# production.net
KiCad netlist of a schematic drawn in EAGLE
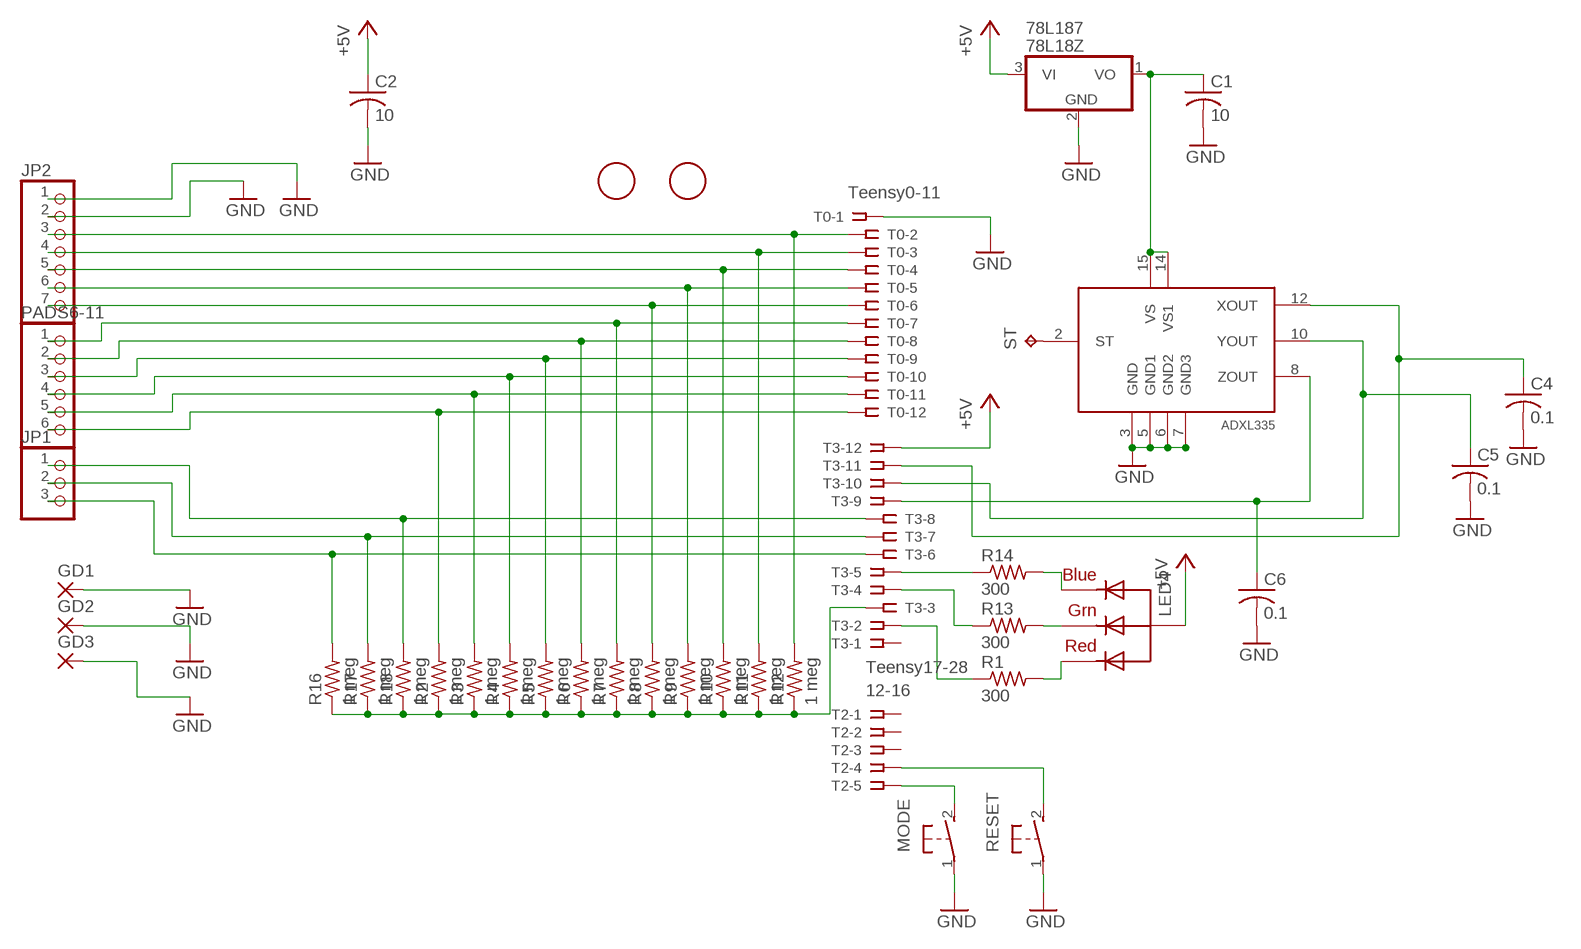
[diagram p0: schematic, sheet 1]

(export (version "E")
  (design (tool "Eeschema 10.0.6"))
  (components
    (comp (ref "78L187")
      (value "78L18Z")
      (footprint "eagle-import:TO92")
      (libsource (lib "eagle-import") (part "78ZL18"))
    )
    (comp (ref "ADXL335")
      (value "ADXL33X")
      (footprint "eagle-import:16LCSP")
      (libsource (lib "eagle-import") (part "ADXL33X"))
    )
    (comp (ref "C1")
      (value "10")
      (footprint "eagle-import:C050-024X044")
      (libsource (lib "eagle-import") (part "C-US050-024X044"))
    )
    (comp (ref "C2")
      (value "10")
      (footprint "eagle-import:C050-024X044")
      (libsource (lib "eagle-import") (part "C-US050-024X044"))
    )
    (comp (ref "C4")
      (value "0.1")
      (footprint "eagle-import:C050-024X044")
      (libsource (lib "eagle-import") (part "C-US050-024X044"))
    )
    (comp (ref "C5")
      (value "0.1")
      (footprint "eagle-import:C050-024X044")
      (libsource (lib "eagle-import") (part "C-US050-024X044"))
    )
    (comp (ref "C6")
      (value "0.1")
      (footprint "eagle-import:C050-024X044")
      (libsource (lib "eagle-import") (part "C-US050-024X044"))
    )
    (comp (ref "FID1")
      (value "FIDUCIAL")
      (footprint "eagle-import:FIDUCIAL_1MM")
      (libsource (lib "eagle-import") (part "FIDUCIAL"))
    )
    (comp (ref "FID2")
      (value "FIDUCIAL")
      (footprint "eagle-import:FIDUCIAL_1MM")
      (libsource (lib "eagle-import") (part "FIDUCIAL"))
    )
    (comp (ref "GD1")
      (value "3,17/1,1")
      (footprint "eagle-import:3,17_1,1")
      (libsource (lib "eagle-import") (part "3,17/1,1"))
    )
    (comp (ref "GD2")
      (value "3,17/1,1")
      (footprint "eagle-import:3,17_1,1")
      (libsource (lib "eagle-import") (part "3,17/1,1"))
    )
    (comp (ref "GD3")
      (value "3,17/1,1")
      (footprint "eagle-import:3,17_1,1")
      (libsource (lib "eagle-import") (part "3,17/1,1"))
    )
    (comp (ref "JP1")
      (value "PINHD-1X3")
      (footprint "eagle-import:1X03")
      (libsource (lib "eagle-import") (part "PINHD-1X3"))
    )
    (comp (ref "JP2")
      (value "PINHD-1X7")
      (footprint "eagle-import:1X07")
      (libsource (lib "eagle-import") (part "PINHD-1X7"))
    )
    (comp (ref "LED4")
      (value "RGBLED_CA-5MM")
      (footprint "eagle-import:LED5MMRGB")
      (libsource (lib "eagle-import") (part "RGBLED_CA-5MM"))
    )
    (comp (ref "MODE")
      (value "31-XX")
      (footprint "eagle-import:B3F-31XX")
      (fields (field (name "MPN") "B3F-3100"))
      (libsource (lib "eagle-import") (part "31-XX"))
    )
    (comp (ref "PADS6-11")
      (value "PINHD-1X6")
      (footprint "eagle-import:1X06")
      (libsource (lib "eagle-import") (part "PINHD-1X6"))
    )
    (comp (ref "R1")
      (value "300")
      (footprint "eagle-import:0207_2V")
      (libsource (lib "eagle-import") (part "R-US_0207/2V"))
    )
    (comp (ref "R2")
      (value "1 meg")
      (footprint "eagle-import:0207_2V")
      (libsource (lib "eagle-import") (part "R-US_0207/2V"))
    )
    (comp (ref "R3")
      (value "1 meg")
      (footprint "eagle-import:0207_2V")
      (libsource (lib "eagle-import") (part "R-US_0207/2V"))
    )
    (comp (ref "R4")
      (value "1 meg")
      (footprint "eagle-import:0207_2V")
      (libsource (lib "eagle-import") (part "R-US_0207/2V"))
    )
    (comp (ref "R5")
      (value "1 meg")
      (footprint "eagle-import:0207_2V")
      (libsource (lib "eagle-import") (part "R-US_0207/2V"))
    )
    (comp (ref "R6")
      (value "1 meg")
      (footprint "eagle-import:0207_2V")
      (libsource (lib "eagle-import") (part "R-US_0207/2V"))
    )
    (comp (ref "R7")
      (value "1 meg")
      (footprint "eagle-import:0207_2V")
      (libsource (lib "eagle-import") (part "R-US_0207/2V"))
    )
    (comp (ref "R8")
      (value "1 meg")
      (footprint "eagle-import:0207_2V")
      (libsource (lib "eagle-import") (part "R-US_0207/2V"))
    )
    (comp (ref "R9")
      (value "1 meg")
      (footprint "eagle-import:0207_2V")
      (libsource (lib "eagle-import") (part "R-US_0207/2V"))
    )
    (comp (ref "R10")
      (value "1 meg")
      (footprint "eagle-import:0207_2V")
      (libsource (lib "eagle-import") (part "R-US_0207/2V"))
    )
    (comp (ref "R11")
      (value "1 meg")
      (footprint "eagle-import:0207_2V")
      (libsource (lib "eagle-import") (part "R-US_0207/2V"))
    )
    (comp (ref "R12")
      (value "1 meg")
      (footprint "eagle-import:0207_2V")
      (libsource (lib "eagle-import") (part "R-US_0207/2V"))
    )
    (comp (ref "R13")
      (value "300")
      (footprint "eagle-import:0207_2V")
      (libsource (lib "eagle-import") (part "R-US_0207/2V"))
    )
    (comp (ref "R14")
      (value "300")
      (footprint "eagle-import:0207_2V")
      (libsource (lib "eagle-import") (part "R-US_0207/2V"))
    )
    (comp (ref "R16")
      (value "1 meg")
      (footprint "eagle-import:0207_2V")
      (libsource (lib "eagle-import") (part "R-US_0207/2V"))
    )
    (comp (ref "R17")
      (value "1 meg")
      (footprint "eagle-import:0207_2V")
      (libsource (lib "eagle-import") (part "R-US_0207/2V"))
    )
    (comp (ref "R18")
      (value "1 meg")
      (footprint "eagle-import:0207_2V")
      (libsource (lib "eagle-import") (part "R-US_0207/2V"))
    )
    (comp (ref "RESET")
      (value "31-XX")
      (footprint "eagle-import:B3F-31XX")
      (fields (field (name "MPN") "B3F-3100"))
      (libsource (lib "eagle-import") (part "31-XX"))
    )
    (comp (ref "ST")
      (value "TPTP17R")
      (footprint "eagle-import:TP17R")
      (libsource (lib "eagle-import") (part "TPTP17R"))
    )
    (comp (ref "T0")
      (value "Teensy0-11")
      (footprint "eagle-import:SSW-112-02-S-S")
      (fields (field (name "MPN") "SSW-112-02-S-S"))
      (libsource (lib "eagle-import") (part "SSW-112-02-S-S"))
    )
    (comp (ref "T2")
      (value "12-16")
      (footprint "eagle-import:SSW-105-02-S-S")
      (fields (field (name "MPN") "SSW-105-02-S-S"))
      (libsource (lib "eagle-import") (part "SSW-105-02-S-S"))
    )
    (comp (ref "T3")
      (value "Teensy17-28")
      (footprint "eagle-import:SSW-112-02-S-S")
      (fields (field (name "MPN") "SSW-112-02-S-S"))
      (libsource (lib "eagle-import") (part "SSW-112-02-S-S"))
    )
  )
  (nets
    (net (code "1") (name "+5V") (class "Default")
      (node (ref "78L187") (pin "3") (pinfunction "VI_3") (pintype "input"))
      (node (ref "C2") (pin "1") (pinfunction "1_1") (pintype "passive"))
      (node (ref "LED4") (pin "2") (pinfunction "VCC_2") (pintype "bidirectional"))
      (node (ref "T3") (pin "12") (pinfunction "1_12") (pintype "passive"))
    )
    (net (code "2") (name "GND") (class "Default")
      (node (ref "78L187") (pin "2") (pinfunction "GND_2") (pintype "passive"))
      (node (ref "ADXL335") (pin "3") (pinfunction "GND_3") (pintype "power_in"))
      (node (ref "ADXL335") (pin "5") (pinfunction "GND1_5") (pintype "power_in"))
      (node (ref "ADXL335") (pin "6") (pinfunction "GND2_6") (pintype "power_in"))
      (node (ref "ADXL335") (pin "7") (pinfunction "GND3_7") (pintype "power_in"))
      (node (ref "C1") (pin "2") (pinfunction "2_2") (pintype "passive"))
      (node (ref "C2") (pin "2") (pinfunction "2_2") (pintype "passive"))
      (node (ref "C4") (pin "2") (pinfunction "2_2") (pintype "passive"))
      (node (ref "C5") (pin "2") (pinfunction "2_2") (pintype "passive"))
      (node (ref "C6") (pin "2") (pinfunction "2_2") (pintype "passive"))
      (node (ref "GD1") (pin "1") (pinfunction "P_1") (pintype "passive"))
      (node (ref "GD2") (pin "1") (pinfunction "P_1") (pintype "passive"))
      (node (ref "GD3") (pin "1") (pinfunction "P_1") (pintype "passive"))
      (node (ref "JP2") (pin "1") (pinfunction "1_1") (pintype "passive"))
      (node (ref "JP2") (pin "2") (pinfunction "2_2") (pintype "passive"))
      (node (ref "MODE") (pin "1") (pinfunction "P_1") (pintype "passive"))
      (node (ref "RESET") (pin "1") (pinfunction "P_1") (pintype "passive"))
      (node (ref "T0") (pin "1") (pinfunction "1_1") (pintype "passive"))
    )
    (net (code "3") (name "Net-(78L187-VO)") (class "Default")
      (node (ref "78L187") (pin "1") (pinfunction "VO_1") (pintype "passive"))
      (node (ref "ADXL335") (pin "14") (pinfunction "VS1_14") (pintype "power_in"))
      (node (ref "ADXL335") (pin "15") (pinfunction "VS_15") (pintype "power_in"))
      (node (ref "C1") (pin "1") (pinfunction "1_1") (pintype "passive"))
    )
    (net (code "4") (name "Net-(ADXL335-ST)") (class "Default")
      (node (ref "ADXL335") (pin "2") (pinfunction "ST_2") (pintype "input"))
      (node (ref "ST") (pin "TP") (pinfunction "TP_TP") (pintype "input"))
    )
    (net (code "5") (name "Net-(ADXL335-XOUT)") (class "Default")
      (node (ref "ADXL335") (pin "12") (pinfunction "XOUT_12") (pintype "output"))
      (node (ref "C4") (pin "1") (pinfunction "1_1") (pintype "passive"))
      (node (ref "T3") (pin "11") (pinfunction "1_11") (pintype "passive"))
    )
    (net (code "6") (name "Net-(ADXL335-YOUT)") (class "Default")
      (node (ref "ADXL335") (pin "10") (pinfunction "YOUT_10") (pintype "output"))
      (node (ref "C5") (pin "1") (pinfunction "1_1") (pintype "passive"))
      (node (ref "T3") (pin "10") (pinfunction "1_10") (pintype "passive"))
    )
    (net (code "7") (name "Net-(ADXL335-ZOUT)") (class "Default")
      (node (ref "ADXL335") (pin "8") (pinfunction "ZOUT_8") (pintype "output"))
      (node (ref "C6") (pin "1") (pinfunction "1_1") (pintype "passive"))
      (node (ref "T3") (pin "9") (pinfunction "1_9") (pintype "passive"))
    )
    (net (code "8") (name "Net-(LED4-BLUE)") (class "Default")
      (node (ref "LED4") (pin "4") (pinfunction "BLUE_4") (pintype "bidirectional"))
      (node (ref "R14") (pin "2") (pinfunction "2_2") (pintype "passive"))
    )
    (net (code "9") (name "Net-(LED4-GREEN)") (class "Default")
      (node (ref "LED4") (pin "3") (pinfunction "GREEN_3") (pintype "bidirectional"))
      (node (ref "R13") (pin "2") (pinfunction "2_2") (pintype "passive"))
    )
    (net (code "10") (name "Net-(LED4-RED)") (class "Default")
      (node (ref "LED4") (pin "1") (pinfunction "RED_1") (pintype "bidirectional"))
      (node (ref "R1") (pin "2") (pinfunction "2_2") (pintype "passive"))
    )
    (net (code "11") (name "Net-(MODE-S)") (class "Default")
      (node (ref "MODE") (pin "2") (pinfunction "S_2") (pintype "passive"))
      (node (ref "T2") (pin "5") (pinfunction "1_5") (pintype "passive"))
    )
    (net (code "12") (name "Net-(RESET-S)") (class "Default")
      (node (ref "RESET") (pin "2") (pinfunction "S_2") (pintype "passive"))
      (node (ref "T2") (pin "4") (pinfunction "1_4") (pintype "passive"))
    )
    (net (code "13") (name "Net-(T0B-1)") (class "Default")
      (node (ref "PADS6-11") (pin "4") (pinfunction "4_4") (pintype "passive"))
      (node (ref "R4") (pin "2") (pinfunction "2_2") (pintype "passive"))
      (node (ref "T0") (pin "10") (pinfunction "1_10") (pintype "passive"))
    )
    (net (code "14") (name "Net-(T0C-1)") (class "Default")
      (node (ref "PADS6-11") (pin "5") (pinfunction "5_5") (pintype "passive"))
      (node (ref "R3") (pin "2") (pinfunction "2_2") (pintype "passive"))
      (node (ref "T0") (pin "11") (pinfunction "1_11") (pintype "passive"))
    )
    (net (code "15") (name "Net-(T0D-1)") (class "Default")
      (node (ref "PADS6-11") (pin "6") (pinfunction "6_6") (pintype "passive"))
      (node (ref "R2") (pin "2") (pinfunction "2_2") (pintype "passive"))
      (node (ref "T0") (pin "12") (pinfunction "1_12") (pintype "passive"))
    )
    (net (code "16") (name "Net-(T0E-1)") (class "Default")
      (node (ref "JP2") (pin "3") (pinfunction "3_3") (pintype "passive"))
      (node (ref "R12") (pin "2") (pinfunction "2_2") (pintype "passive"))
      (node (ref "T0") (pin "2") (pinfunction "1_2") (pintype "passive"))
    )
    (net (code "17") (name "Net-(T0F-1)") (class "Default")
      (node (ref "JP2") (pin "4") (pinfunction "4_4") (pintype "passive"))
      (node (ref "R11") (pin "2") (pinfunction "2_2") (pintype "passive"))
      (node (ref "T0") (pin "3") (pinfunction "1_3") (pintype "passive"))
    )
    (net (code "18") (name "Net-(T0G-1)") (class "Default")
      (node (ref "JP2") (pin "5") (pinfunction "5_5") (pintype "passive"))
      (node (ref "R10") (pin "2") (pinfunction "2_2") (pintype "passive"))
      (node (ref "T0") (pin "4") (pinfunction "1_4") (pintype "passive"))
    )
    (net (code "19") (name "Net-(T0H-1)") (class "Default")
      (node (ref "JP2") (pin "6") (pinfunction "6_6") (pintype "passive"))
      (node (ref "R9") (pin "2") (pinfunction "2_2") (pintype "passive"))
      (node (ref "T0") (pin "5") (pinfunction "1_5") (pintype "passive"))
    )
    (net (code "20") (name "Net-(T0I-1)") (class "Default")
      (node (ref "JP2") (pin "7") (pinfunction "7_7") (pintype "passive"))
      (node (ref "R8") (pin "2") (pinfunction "2_2") (pintype "passive"))
      (node (ref "T0") (pin "6") (pinfunction "1_6") (pintype "passive"))
    )
    (net (code "21") (name "Net-(T0J-1)") (class "Default")
      (node (ref "PADS6-11") (pin "1") (pinfunction "1_1") (pintype "passive"))
      (node (ref "R7") (pin "2") (pinfunction "2_2") (pintype "passive"))
      (node (ref "T0") (pin "7") (pinfunction "1_7") (pintype "passive"))
    )
    (net (code "22") (name "Net-(T0K-1)") (class "Default")
      (node (ref "PADS6-11") (pin "2") (pinfunction "2_2") (pintype "passive"))
      (node (ref "R6") (pin "2") (pinfunction "2_2") (pintype "passive"))
      (node (ref "T0") (pin "8") (pinfunction "1_8") (pintype "passive"))
    )
    (net (code "23") (name "Net-(T0L-1)") (class "Default")
      (node (ref "PADS6-11") (pin "3") (pinfunction "3_3") (pintype "passive"))
      (node (ref "R5") (pin "2") (pinfunction "2_2") (pintype "passive"))
      (node (ref "T0") (pin "9") (pinfunction "1_9") (pintype "passive"))
    )
    (net (code "24") (name "Net-(T3E-1)") (class "Default")
      (node (ref "R1") (pin "1") (pinfunction "1_1") (pintype "passive"))
      (node (ref "T3") (pin "2") (pinfunction "1_2") (pintype "passive"))
    )
    (net (code "25") (name "Net-(T3F-1)") (class "Default")
      (node (ref "R10") (pin "1") (pinfunction "1_1") (pintype "passive"))
      (node (ref "R11") (pin "1") (pinfunction "1_1") (pintype "passive"))
      (node (ref "R12") (pin "1") (pinfunction "1_1") (pintype "passive"))
      (node (ref "R16") (pin "1") (pinfunction "1_1") (pintype "passive"))
      (node (ref "R17") (pin "1") (pinfunction "1_1") (pintype "passive"))
      (node (ref "R18") (pin "1") (pinfunction "1_1") (pintype "passive"))
      (node (ref "R2") (pin "1") (pinfunction "1_1") (pintype "passive"))
      (node (ref "R3") (pin "1") (pinfunction "1_1") (pintype "passive"))
      (node (ref "R4") (pin "1") (pinfunction "1_1") (pintype "passive"))
      (node (ref "R5") (pin "1") (pinfunction "1_1") (pintype "passive"))
      (node (ref "R6") (pin "1") (pinfunction "1_1") (pintype "passive"))
      (node (ref "R7") (pin "1") (pinfunction "1_1") (pintype "passive"))
      (node (ref "R8") (pin "1") (pinfunction "1_1") (pintype "passive"))
      (node (ref "R9") (pin "1") (pinfunction "1_1") (pintype "passive"))
      (node (ref "T3") (pin "3") (pinfunction "1_3") (pintype "passive"))
    )
    (net (code "26") (name "Net-(T3G-1)") (class "Default")
      (node (ref "R13") (pin "1") (pinfunction "1_1") (pintype "passive"))
      (node (ref "T3") (pin "4") (pinfunction "1_4") (pintype "passive"))
    )
    (net (code "27") (name "Net-(T3H-1)") (class "Default")
      (node (ref "R14") (pin "1") (pinfunction "1_1") (pintype "passive"))
      (node (ref "T3") (pin "5") (pinfunction "1_5") (pintype "passive"))
    )
    (net (code "28") (name "Net-(T3I-1)") (class "Default")
      (node (ref "JP1") (pin "3") (pinfunction "3_3") (pintype "passive"))
      (node (ref "R16") (pin "2") (pinfunction "2_2") (pintype "passive"))
      (node (ref "T3") (pin "6") (pinfunction "1_6") (pintype "passive"))
    )
    (net (code "29") (name "Net-(T3J-1)") (class "Default")
      (node (ref "JP1") (pin "2") (pinfunction "2_2") (pintype "passive"))
      (node (ref "R17") (pin "2") (pinfunction "2_2") (pintype "passive"))
      (node (ref "T3") (pin "7") (pinfunction "1_7") (pintype "passive"))
    )
    (net (code "30") (name "Net-(T3K-1)") (class "Default")
      (node (ref "JP1") (pin "1") (pinfunction "1_1") (pintype "passive"))
      (node (ref "R18") (pin "2") (pinfunction "2_2") (pintype "passive"))
      (node (ref "T3") (pin "8") (pinfunction "1_8") (pintype "passive"))
    )
    (net (code "31") (name "unconnected-(T2-Pad1)") (class "Default")
      (node (ref "T2") (pin "1") (pinfunction "1_1") (pintype "passive"))
    )
    (net (code "32") (name "unconnected-(T2B-1-Pad2)") (class "Default")
      (node (ref "T2") (pin "2") (pinfunction "1_2") (pintype "passive"))
    )
    (net (code "33") (name "unconnected-(T2C-1-Pad3)") (class "Default")
      (node (ref "T2") (pin "3") (pinfunction "1_3") (pintype "passive"))
    )
    (net (code "34") (name "unconnected-(T3-Pad1)") (class "Default")
      (node (ref "T3") (pin "1") (pinfunction "1_1") (pintype "passive"))
    )
  )
)
